# LPS_main.net
KiCad netlist of a schematic drawn in Altium Designer
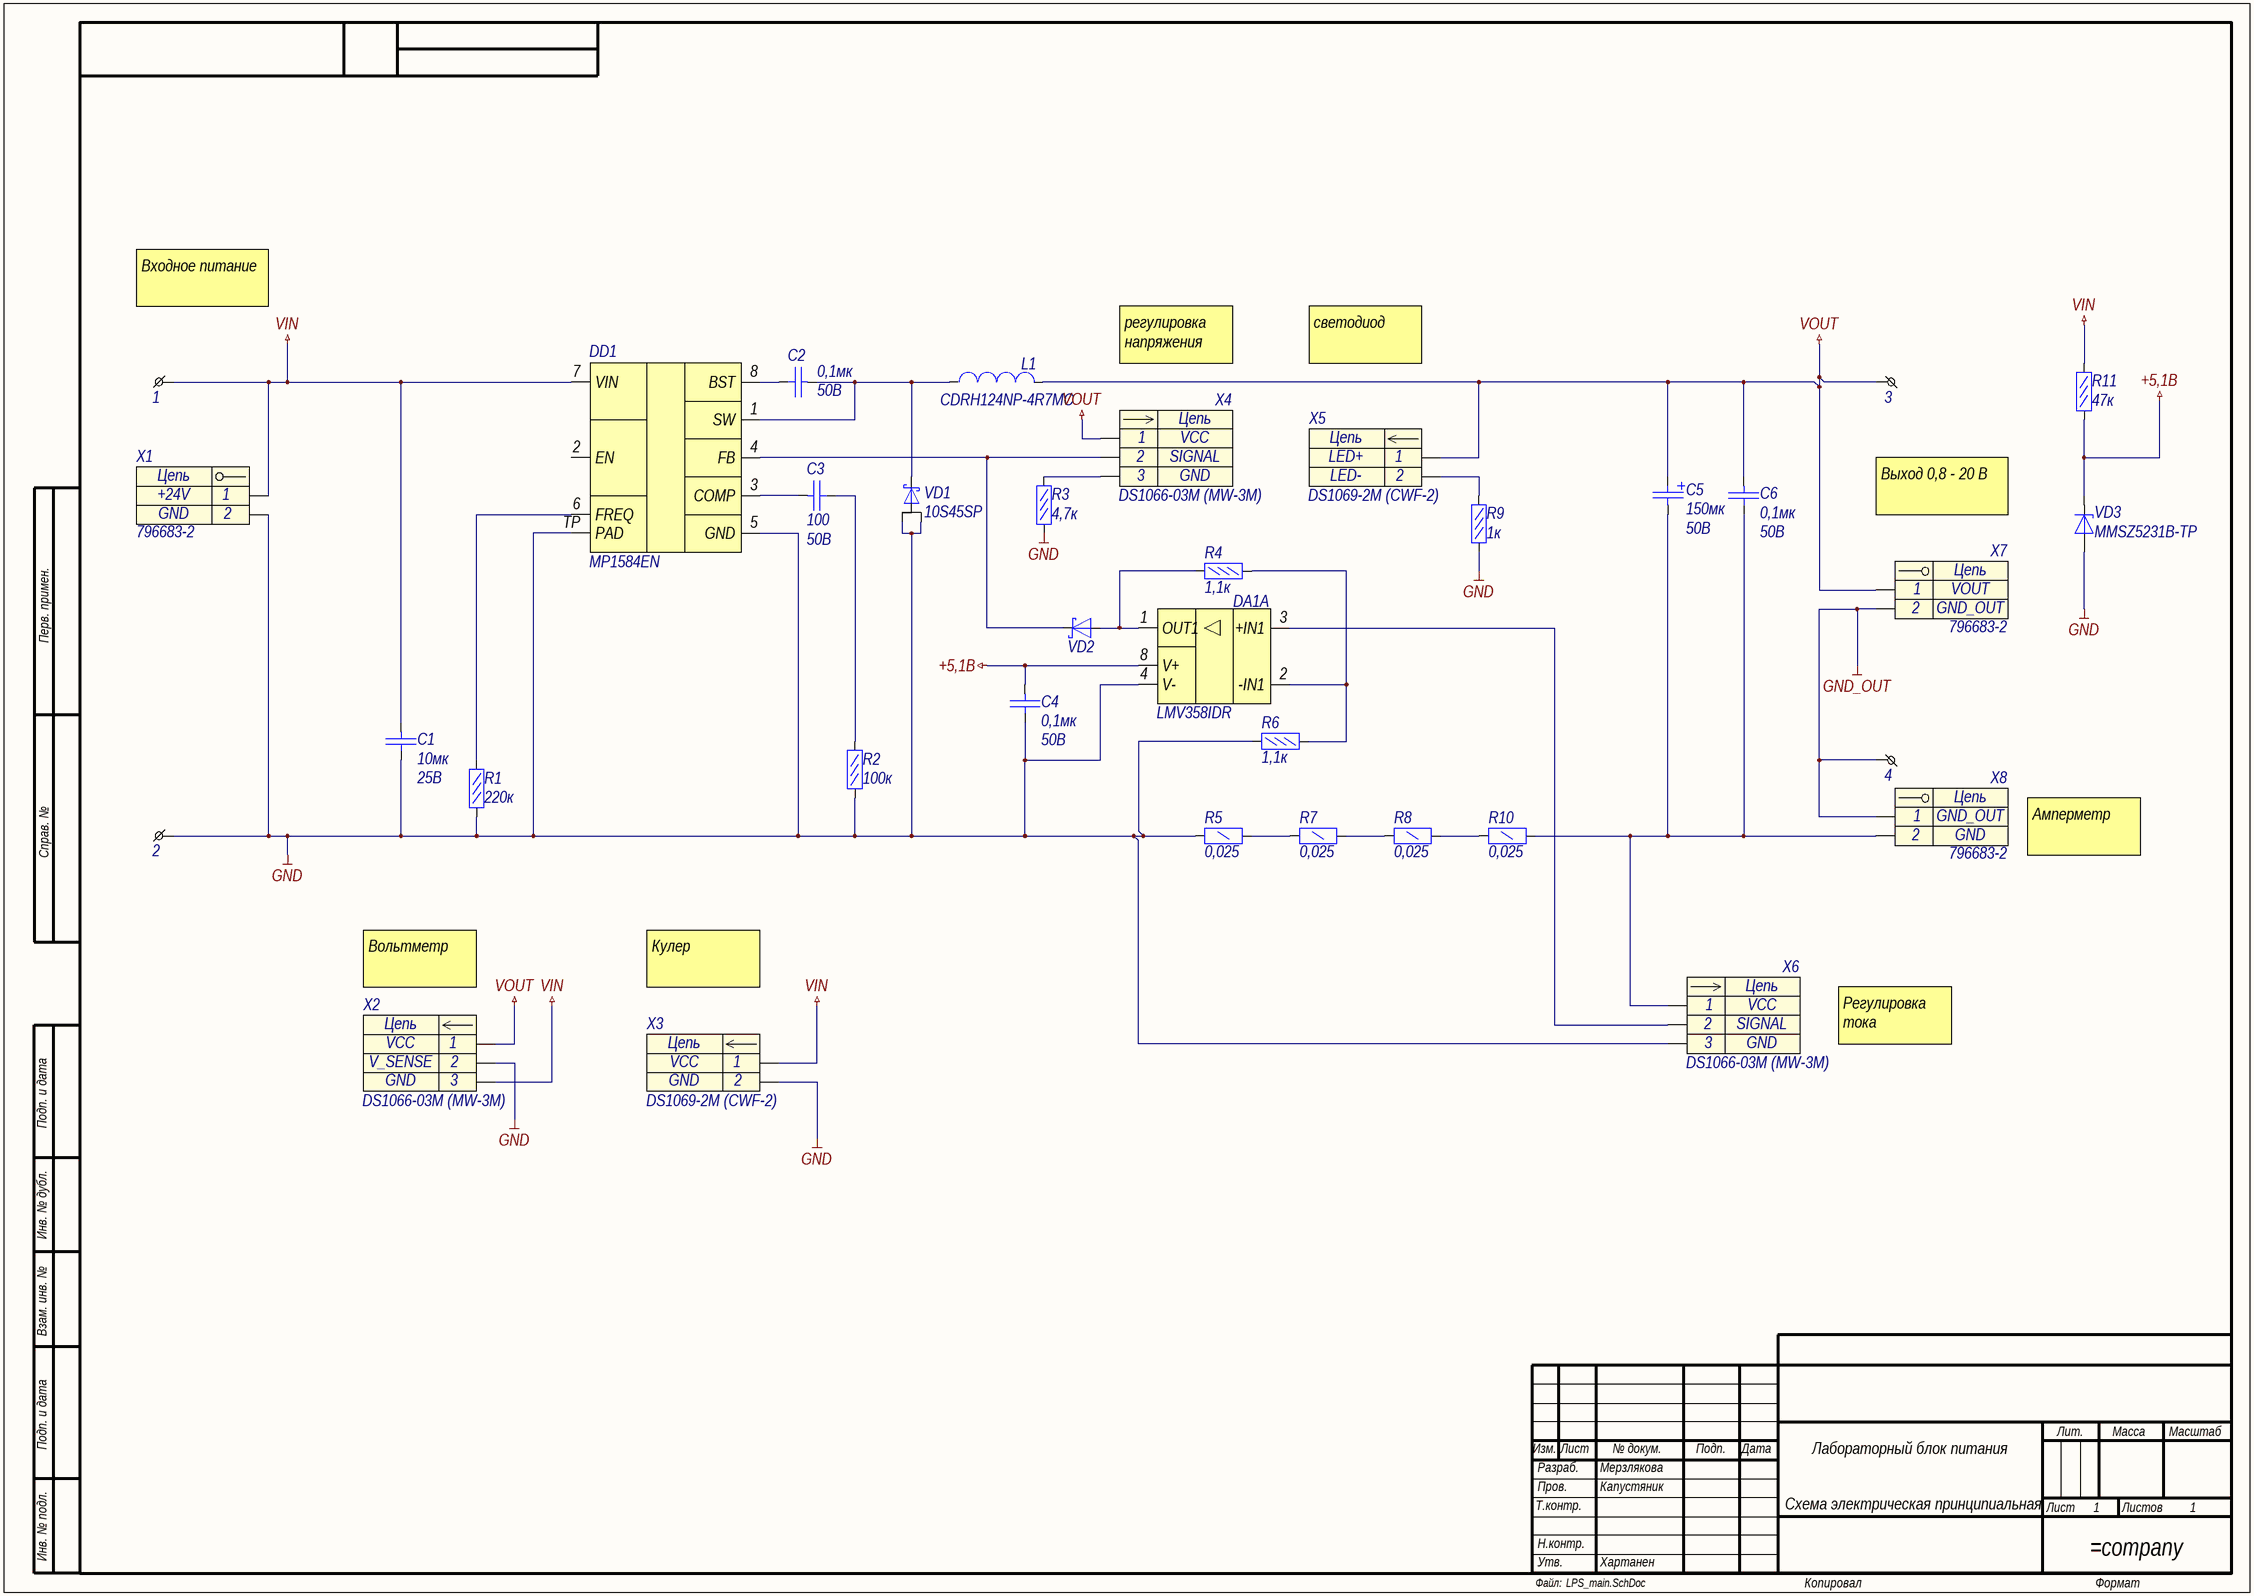
[diagram p0: LPS_main.SchDoc]

(export (version "E")
  (design (tool "Eeschema 10.0.6"))
  (components
    (comp (ref "1")
      (value "SOLDER_PAD")
      (footprint "PAD_5_8mm")
      (libsource (lib "mount_parts") (part "SOLDER_PAD"))
    )
    (comp (ref "2")
      (value "SOLDER_PAD")
      (footprint "PAD_5_8mm")
      (libsource (lib "mount_parts") (part "SOLDER_PAD"))
    )
    (comp (ref "3")
      (value "SOLDER_PAD")
      (footprint "PAD_5_8mm")
      (libsource (lib "mount_parts") (part "SOLDER_PAD"))
    )
    (comp (ref "4")
      (value "SOLDER_PAD")
      (footprint "PAD_5_8mm")
      (libsource (lib "mount_parts") (part "SOLDER_PAD"))
    )
    (comp (ref "C1")
      (value "10мк")
      (footprint "C1206")
      (description "Конденсатор кер. 10мкФ 25В")
      (fields (field (name "MANUFACTURER") "Yageo") (field (name "VOLTAGE") "25В"))
      (libsource (lib "capacitors") (part "CC1206KKX7R8BB106"))
    )
    (comp (ref "C2")
      (value "0,1мк")
      (footprint "C0603")
      (description "Конденсатор кер. 0,1мкФ 50В")
      (fields (field (name "MANUFACTURER") "Yageo") (field (name "VOLTAGE") "50В"))
      (libsource (lib "capacitors") (part "CC0603JPX7R9BB104"))
    )
    (comp (ref "C3")
      (value "100")
      (footprint "C0603")
      (description "Конденсатор кер. 100пФ 50В")
      (fields (field (name "MANUFACTURER") "Yageo") (field (name "VOLTAGE") "50В"))
      (libsource (lib "capacitors") (part "CC0603JRNPO9BN101"))
    )
    (comp (ref "C4")
      (value "0,1мк")
      (footprint "C0603")
      (description "Конденсатор кер. 0,1мкФ 50В")
      (fields (field (name "MANUFACTURER") "Yageo") (field (name "VOLTAGE") "50В"))
      (libsource (lib "capacitors") (part "CC0603JPX7R9BB104"))
    )
    (comp (ref "C5")
      (value "150мк")
      (footprint "CAPALUM_10x12.5")
      (description "Конденсатор эл.лит. алюм. 150мкФ 50В")
      (fields (field (name "MANUFACTURER") "EPCOS") (field (name "VOLTAGE") "50В"))
      (libsource (lib "capacitors") (part "B41858C6157M"))
    )
    (comp (ref "C6")
      (value "0,1мк")
      (footprint "C0603")
      (description "Конденсатор кер. 0,1мкФ 50В")
      (fields (field (name "MANUFACTURER") "Yageo") (field (name "VOLTAGE") "50В"))
      (libsource (lib "capacitors") (part "CC0603JPX7R9BB104"))
    )
    (comp (ref "DA1")
      (value "LMV358IDR")
      (footprint "SOIC-8")
      (description "Сдвоенный операционнй усилитель 2.7-5В CMOS Rail-to-rail")
      (fields (field (name "MANUFACTURER") "TI") (field (name "NAME") "LMV358IDR"))
      (libsource (lib "ics") (part "LMV358IDR"))
    )
    (comp (ref "DD1")
      (value "MP1584EN")
      (footprint "SOIC-8 with PAD")
      (description "регулируемый стабилизатор напряжения")
      (libsource (lib "ics") (part "MP1584EN"))
    )
    (comp (ref "L1")
      (value "CDRH124NP-4R7MC")
      (footprint "CDRH124")
      (description "Катушка с сердечником 4,7мкГн 0,8А")
      (libsource (lib "inductance") (part "CDRH124NP-4R7MC"))
    )
    (comp (ref "R1")
      (value "220к")
      (footprint "R0603")
      (description "Резистор 220кОм 0,1Вт 1%")
      (fields (field (name "MANUFACTURER") "YAGEO") (field (name "TOLERANCE") "1%"))
      (libsource (lib "resistors") (part "RC0603FR-07220KL"))
    )
    (comp (ref "R2")
      (value "100к")
      (footprint "R0603")
      (description "Резистор 100кОм 0,1Вт 1%")
      (fields (field (name "MANUFACTURER") "YAGEO") (field (name "TOLERANCE") "1%"))
      (libsource (lib "resistors") (part "RC0603FR-07100KL"))
    )
    (comp (ref "R3")
      (value "4,7к")
      (footprint "R0603")
      (description "Резистор 4,7кОм 0,063Вт 1%")
      (fields (field (name "MANUFACTURER") "YAGEO") (field (name "TOLERANCE") "1%"))
      (libsource (lib "resistors") (part "RC0603FR-074K7L"))
    )
    (comp (ref "R4")
      (value "1,1к")
      (footprint "R0603")
      (description "Резистор 1,1кОм 0,063Вт 1%")
      (fields (field (name "MANUFACTURER") "YAGEO") (field (name "TOLERANCE") "1%"))
      (libsource (lib "resistors") (part "RC0603FR-071K1L"))
    )
    (comp (ref "R5")
      (value "0,025")
      (footprint "R1206")
      (description "Резистор 180к 0,25Вт 1%")
      (fields (field (name "MANUFACTURER") "YAGEO"))
      (libsource (lib "resistors") (part "RC1206FR-07180KL"))
    )
    (comp (ref "R6")
      (value "1,1к")
      (footprint "R0603")
      (description "Резистор 1,1кОм 0,063Вт 1%")
      (fields (field (name "MANUFACTURER") "YAGEO") (field (name "TOLERANCE") "1%"))
      (libsource (lib "") (part "RC0603FR-071K1L_1"))
    )
    (comp (ref "R7")
      (value "0,025")
      (footprint "R1206")
      (description "Резистор 180к 0,25Вт 1%")
      (fields (field (name "MANUFACTURER") "YAGEO"))
      (libsource (lib "resistors") (part "RC1206FR-07180KL"))
    )
    (comp (ref "R8")
      (value "0,025")
      (footprint "R1206")
      (description "Резистор 180к 0,25Вт 1%")
      (fields (field (name "MANUFACTURER") "YAGEO"))
      (libsource (lib "resistors") (part "RC1206FR-07180KL"))
    )
    (comp (ref "R9")
      (value "1к")
      (footprint "R0603")
      (description "Резистор 1кОм 0,063Вт 1%")
      (fields (field (name "MANUFACTURER") "YAGEO") (field (name "TOLERANCE") "1%"))
      (libsource (lib "resistors") (part "RC0603FR-071KL"))
    )
    (comp (ref "R10")
      (value "0,025")
      (footprint "R1206")
      (description "Резистор 180к 0,25Вт 1%")
      (fields (field (name "MANUFACTURER") "YAGEO"))
      (libsource (lib "resistors") (part "RC1206FR-07180KL"))
    )
    (comp (ref "R11")
      (value "47к")
      (footprint "R0603")
      (description "Резистор 47кОм 0,063Вт 1%")
      (fields (field (name "MANUFACTURER") "YAGEO") (field (name "TOLERANCE") "1%"))
      (libsource (lib "resistors") (part "RC0603FR-0747KL"))
    )
    (comp (ref "VD1")
      (value "10S45SP")
      (footprint "TO-277A")
      (description "Диод Шоттки 45В 10А")
      (fields (field (name "MANUFACTURER") "YFW") (field (name "NAME") "10S45SP"))
      (libsource (lib "diodes") (part "10S45SP"))
    )
    (comp (ref "VD2")
      (value "1N5817WS")
      (footprint "SOD323")
      (description "Диод Шоттки 1N5817WS 20V 1А 0.45V")
      (fields (field (name "VOLTAGE") "20В"))
      (libsource (lib "diodes") (part "1N5817WS"))
    )
    (comp (ref "VD3")
      (value "MMSZ5231B-TP")
      (footprint "SOD123")
      (description "Стабилитрон 5,1В")
      (libsource (lib "diodes") (part "MMSZ5231B-TP"))
    )
    (comp (ref "X1")
      (value "796683-2")
      (footprint "796683-2")
      (description "Винтовой клеммник (наборный 2х2)")
      (fields (field (name "NAME") "796683-2"))
      (libsource (lib "headers") (part "796683-2"))
    )
    (comp (ref "X2")
      (value "DS1066-03M (MW-3M)")
      (footprint "MW-3M")
      (description "Разъем - 3 конт. прямая вилка на плату")
      (fields (field (name "NAME") "DS1066-03M (MW-3M)"))
      (libsource (lib "") (part "MW-3M_1"))
    )
    (comp (ref "X3")
      (value "DS1069-2M (CWF-2)")
      (footprint "CWF-2")
      (description "Разъем - 2 конт. прямая вилка на плату")
      (fields (field (name "NAME") "DS1069-2M (CWF-2)"))
      (libsource (lib "headers") (part "CWF-2"))
    )
    (comp (ref "X4")
      (value "DS1066-03M (MW-3M)")
      (footprint "MW-3M")
      (description "Разъем - 3 конт. прямая вилка на плату")
      (fields (field (name "NAME") "DS1066-03M (MW-3M)"))
      (libsource (lib "headers") (part "MW-3M"))
    )
    (comp (ref "X5")
      (value "DS1069-2M (CWF-2)")
      (footprint "CWF-2")
      (description "Разъем - 2 конт. прямая вилка на плату")
      (fields (field (name "NAME") "DS1069-2M (CWF-2)"))
      (libsource (lib "headers") (part "CWF-2"))
    )
    (comp (ref "X6")
      (value "DS1066-03M (MW-3M)")
      (footprint "MW-3M")
      (description "Разъем - 3 конт. прямая вилка на плату")
      (fields (field (name "NAME") "DS1066-03M (MW-3M)"))
      (libsource (lib "headers") (part "MW-3M"))
    )
    (comp (ref "X7")
      (value "796683-2")
      (footprint "796683-2")
      (description "Винтовой клеммник (наборный 2х2)")
      (fields (field (name "NAME") "796683-2"))
      (libsource (lib "") (part "796683-2_1"))
    )
    (comp (ref "X8")
      (value "796683-2")
      (footprint "796683-2")
      (description "Винтовой клеммник (наборный 2х2)")
      (fields (field (name "NAME") "796683-2"))
      (libsource (lib "") (part "796683-2_1"))
    )
  )
  (nets
    (net (code "1") (name "+5,1В") (class "Default")
      (node (ref "C4") (pin "2") (pinfunction "2_2") (pintype "passive"))
      (node (ref "DA1") (pin "8") (pinfunction "V+_8") (pintype "passive"))
      (node (ref "R11") (pin "2") (pinfunction "2_2") (pintype "passive"))
      (node (ref "VD3") (pin "1") (pinfunction "K_1") (pintype "passive"))
    )
    (net (code "2") (name "GND") (class "Default")
      (node (ref "2") (pin "1") (pinfunction "1_1") (pintype "passive"))
      (node (ref "C1") (pin "1") (pinfunction "1_1") (pintype "passive"))
      (node (ref "C4") (pin "1") (pinfunction "1_1") (pintype "passive"))
      (node (ref "DA1") (pin "4") (pinfunction "V-_4") (pintype "passive"))
      (node (ref "DD1") (pin "5") (pinfunction "GND_5") (pintype "passive"))
      (node (ref "DD1") (pin "TP") (pinfunction "PAD_TP") (pintype "passive"))
      (node (ref "R1") (pin "1") (pinfunction "1_1") (pintype "passive"))
      (node (ref "R2") (pin "2") (pinfunction "2_2") (pintype "passive"))
      (node (ref "R3") (pin "1") (pinfunction "1_1") (pintype "passive"))
      (node (ref "R5") (pin "1") (pinfunction "1_1") (pintype "passive"))
      (node (ref "R6") (pin "2") (pinfunction "2_2") (pintype "passive"))
      (node (ref "R9") (pin "1") (pinfunction "1_1") (pintype "passive"))
      (node (ref "VD1") (pin "1") (pinfunction "A_1") (pintype "passive"))
      (node (ref "VD1") (pin "2") (pinfunction "A_2") (pintype "passive"))
      (node (ref "VD3") (pin "2") (pinfunction "A_2") (pintype "passive"))
      (node (ref "X1") (pin "2") (pinfunction "2_2") (pintype "passive"))
      (node (ref "X2") (pin "2") (pinfunction "2_2") (pintype "passive"))
      (node (ref "X3") (pin "2") (pinfunction "2_2") (pintype "passive"))
      (node (ref "X6") (pin "3") (pinfunction "3_3") (pintype "passive"))
    )
    (net (code "3") (name "GND_OUT") (class "Default")
      (node (ref "4") (pin "1") (pinfunction "1_1") (pintype "passive"))
      (node (ref "X7") (pin "2") (pinfunction "2_2") (pintype "passive"))
      (node (ref "X8") (pin "1") (pinfunction "1_1") (pintype "passive"))
    )
    (net (code "4") (name "Net-(C3-Pad1)") (class "Default")
      (node (ref "C3") (pin "1") (pinfunction "1_1") (pintype "passive"))
      (node (ref "R2") (pin "1") (pinfunction "1_1") (pintype "passive"))
    )
    (net (code "5") (name "Net-(C5-Pad2)") (class "Default")
      (node (ref "C5") (pin "2") (pinfunction "2_2") (pintype "passive"))
      (node (ref "C6") (pin "1") (pinfunction "1_1") (pintype "passive"))
      (node (ref "R10") (pin "2") (pinfunction "2_2") (pintype "passive"))
      (node (ref "X6") (pin "1") (pinfunction "1_1") (pintype "passive"))
      (node (ref "X8") (pin "2") (pinfunction "2_2") (pintype "passive"))
    )
    (net (code "6") (name "Net-(DA1A-+IN1)") (class "Default")
      (node (ref "DA1") (pin "3") (pinfunction "+IN1_3") (pintype "passive"))
      (node (ref "X6") (pin "2") (pinfunction "2_2") (pintype "passive"))
    )
    (net (code "7") (name "Net-(DA1A--IN1)") (class "Default")
      (node (ref "DA1") (pin "2") (pinfunction "-IN1_2") (pintype "passive"))
      (node (ref "R4") (pin "2") (pinfunction "2_2") (pintype "passive"))
      (node (ref "R6") (pin "1") (pinfunction "1_1") (pintype "passive"))
    )
    (net (code "8") (name "Net-(DA1A-OUT1)") (class "Default")
      (node (ref "DA1") (pin "1") (pinfunction "OUT1_1") (pintype "passive"))
      (node (ref "R4") (pin "1") (pinfunction "1_1") (pintype "passive"))
      (node (ref "VD2") (pin "2") (pinfunction "A_2") (pintype "passive"))
    )
    (net (code "9") (name "Net-(DD1-BST)") (class "Default")
      (node (ref "C2") (pin "1") (pinfunction "1_1") (pintype "passive"))
      (node (ref "DD1") (pin "8") (pinfunction "BST_8") (pintype "passive"))
    )
    (net (code "10") (name "Net-(DD1-COMP)") (class "Default")
      (node (ref "C3") (pin "2") (pinfunction "2_2") (pintype "passive"))
      (node (ref "DD1") (pin "3") (pinfunction "COMP_3") (pintype "passive"))
    )
    (net (code "11") (name "Net-(DD1-FB)") (class "Default")
      (node (ref "DD1") (pin "4") (pinfunction "FB_4") (pintype "passive"))
      (node (ref "VD2") (pin "1") (pinfunction "K_1") (pintype "passive"))
      (node (ref "X4") (pin "2") (pinfunction "2_2") (pintype "passive"))
    )
    (net (code "12") (name "Net-(DD1-FREQ)") (class "Default")
      (node (ref "DD1") (pin "6") (pinfunction "FREQ_6") (pintype "passive"))
      (node (ref "R1") (pin "2") (pinfunction "2_2") (pintype "passive"))
    )
    (net (code "13") (name "Net-(DD1-SW)") (class "Default")
      (node (ref "C2") (pin "2") (pinfunction "2_2") (pintype "passive"))
      (node (ref "DD1") (pin "1") (pinfunction "SW_1") (pintype "passive"))
      (node (ref "L1") (pin "1") (pinfunction "3_1") (pintype "passive"))
      (node (ref "VD1") (pin "3") (pinfunction "K_3") (pintype "passive"))
    )
    (net (code "14") (name "Net-(R3-Pad2)") (class "Default")
      (node (ref "R3") (pin "2") (pinfunction "2_2") (pintype "passive"))
      (node (ref "X4") (pin "3") (pinfunction "3_3") (pintype "passive"))
    )
    (net (code "15") (name "Net-(R5-Pad2)") (class "Default")
      (node (ref "R5") (pin "2") (pinfunction "2_2") (pintype "passive"))
      (node (ref "R7") (pin "1") (pinfunction "1_1") (pintype "passive"))
    )
    (net (code "16") (name "Net-(R7-Pad2)") (class "Default")
      (node (ref "R7") (pin "2") (pinfunction "2_2") (pintype "passive"))
      (node (ref "R8") (pin "1") (pinfunction "1_1") (pintype "passive"))
    )
    (net (code "17") (name "Net-(R9-Pad2)") (class "Default")
      (node (ref "R9") (pin "2") (pinfunction "2_2") (pintype "passive"))
      (node (ref "X5") (pin "2") (pinfunction "2_2") (pintype "passive"))
    )
    (net (code "18") (name "Net-(R10-Pad1)") (class "Default")
      (node (ref "R10") (pin "1") (pinfunction "1_1") (pintype "passive"))
      (node (ref "R8") (pin "2") (pinfunction "2_2") (pintype "passive"))
    )
    (net (code "19") (name "VIN") (class "Default")
      (node (ref "1") (pin "1") (pinfunction "1_1") (pintype "passive"))
      (node (ref "C1") (pin "2") (pinfunction "2_2") (pintype "passive"))
      (node (ref "DD1") (pin "7") (pinfunction "VIN_7") (pintype "passive"))
      (node (ref "R11") (pin "1") (pinfunction "1_1") (pintype "passive"))
      (node (ref "X1") (pin "1") (pinfunction "1_1") (pintype "passive"))
      (node (ref "X2") (pin "3") (pinfunction "3_3") (pintype "passive"))
      (node (ref "X3") (pin "1") (pinfunction "1_1") (pintype "passive"))
    )
    (net (code "20") (name "VOUT") (class "Default")
      (node (ref "3") (pin "1") (pinfunction "1_1") (pintype "passive"))
      (node (ref "C5") (pin "1") (pinfunction "1_1") (pintype "passive"))
      (node (ref "C6") (pin "2") (pinfunction "2_2") (pintype "passive"))
      (node (ref "L1") (pin "2") (pinfunction "4_2") (pintype "passive"))
      (node (ref "X2") (pin "1") (pinfunction "1_1") (pintype "passive"))
      (node (ref "X4") (pin "1") (pinfunction "1_1") (pintype "passive"))
      (node (ref "X5") (pin "1") (pinfunction "1_1") (pintype "passive"))
      (node (ref "X7") (pin "1") (pinfunction "1_1") (pintype "passive"))
    )
    (net (code "21") (name "unconnected-(DD1-EN-Pad2)") (class "Default")
      (node (ref "DD1") (pin "2") (pinfunction "EN_2") (pintype "passive"))
    )
  )
)
